# Sheet1.net
KiCad netlist of a schematic drawn in Altium Designer
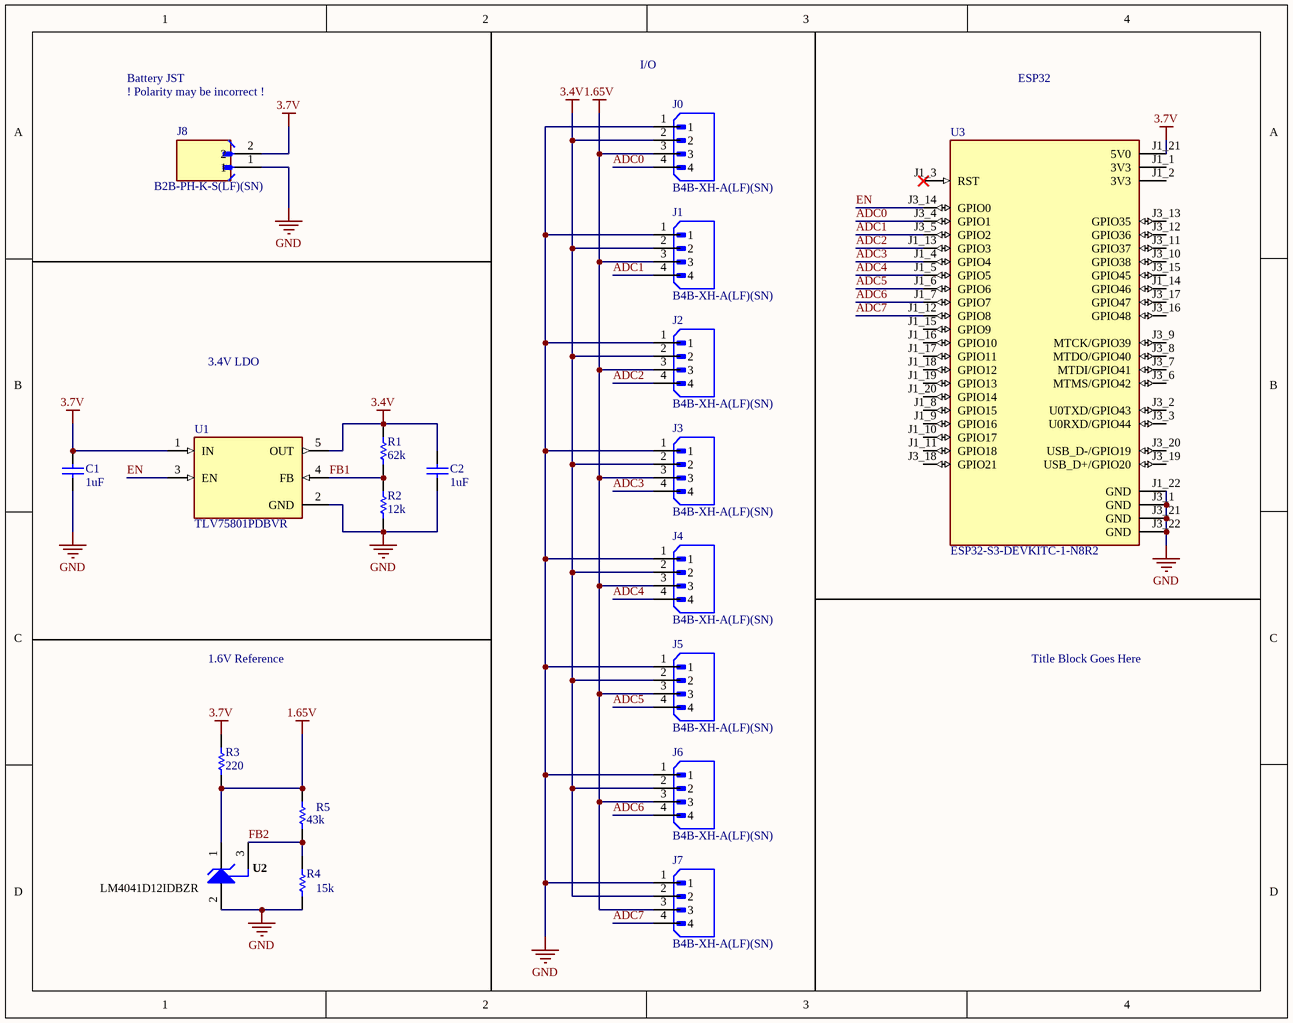
[diagram p0: Sheet1.SchDoc]

(export (version "E")
  (design (tool "Eeschema 10.0.6"))
  (components
    (comp (ref "C1")
      (value "1uF")
      (footprint "CAPC3216X110X50LL20T25")
      (description "Chip Capacitor, 1 uF, +/- 10%, 50 V, -55 to 125 degC, 1206 (3216 Metric), RoHS, Tape and Reel")
      (fields (field (name "MANUFACTURER") "Kemet") (field (name "TOLERANCE") "10%"))
      (libsource (lib "Altium Content Vault") (part "CAP-NP-2"))
    )
    (comp (ref "C2")
      (value "1uF")
      (footprint "CAPC3216X110X50LL20T25")
      (description "Chip Capacitor, 1 uF, +/- 10%, 50 V, -55 to 125 degC, 1206 (3216 Metric), RoHS, Tape and Reel")
      (fields (field (name "MANUFACTURER") "Kemet") (field (name "TOLERANCE") "10%"))
      (libsource (lib "Altium Content Vault") (part "CAP-NP-2"))
    )
    (comp (ref "J0")
      (value "B4B-XH-A(LF)(SN)")
      (footprint "JST_B4B-XH-A(LF)(SN)")
      (description "Connector Header Through Hole 4 position 0.098 (2.50mm)")
      (fields (field (name "MF") "JST Sales"))
      (libsource (lib "B4B-XH-A_LF__SN_") (part "B4B-XH-A(LF)(SN)"))
    )
    (comp (ref "J1")
      (value "B4B-XH-A(LF)(SN)")
      (footprint "JST_B4B-XH-A(LF)(SN)")
      (description "Connector Header Through Hole 4 position 0.098 (2.50mm)")
      (fields (field (name "MF") "JST Sales"))
      (libsource (lib "B4B-XH-A_LF__SN_") (part "B4B-XH-A(LF)(SN)"))
    )
    (comp (ref "J2")
      (value "B4B-XH-A(LF)(SN)")
      (footprint "JST_B4B-XH-A(LF)(SN)")
      (description "Connector Header Through Hole 4 position 0.098 (2.50mm)")
      (fields (field (name "MF") "JST Sales"))
      (libsource (lib "B4B-XH-A_LF__SN_") (part "B4B-XH-A(LF)(SN)"))
    )
    (comp (ref "J3")
      (value "B4B-XH-A(LF)(SN)")
      (footprint "JST_B4B-XH-A(LF)(SN)")
      (description "Connector Header Through Hole 4 position 0.098 (2.50mm)")
      (fields (field (name "MF") "JST Sales"))
      (libsource (lib "B4B-XH-A_LF__SN_") (part "B4B-XH-A(LF)(SN)"))
    )
    (comp (ref "J4")
      (value "B4B-XH-A(LF)(SN)")
      (footprint "JST_B4B-XH-A(LF)(SN)")
      (description "Connector Header Through Hole 4 position 0.098 (2.50mm)")
      (fields (field (name "MF") "JST Sales"))
      (libsource (lib "B4B-XH-A_LF__SN_") (part "B4B-XH-A(LF)(SN)"))
    )
    (comp (ref "J5")
      (value "B4B-XH-A(LF)(SN)")
      (footprint "JST_B4B-XH-A(LF)(SN)")
      (description "Connector Header Through Hole 4 position 0.098 (2.50mm)")
      (fields (field (name "MF") "JST Sales"))
      (libsource (lib "B4B-XH-A_LF__SN_") (part "B4B-XH-A(LF)(SN)"))
    )
    (comp (ref "J6")
      (value "B4B-XH-A(LF)(SN)")
      (footprint "JST_B4B-XH-A(LF)(SN)")
      (description "Connector Header Through Hole 4 position 0.098 (2.50mm)")
      (fields (field (name "MF") "JST Sales"))
      (libsource (lib "B4B-XH-A_LF__SN_") (part "B4B-XH-A(LF)(SN)"))
    )
    (comp (ref "J7")
      (value "B4B-XH-A(LF)(SN)")
      (footprint "JST_B4B-XH-A(LF)(SN)")
      (description "Connector Header Through Hole 4 position 0.098 (2.50mm)")
      (fields (field (name "MF") "JST Sales"))
      (libsource (lib "B4B-XH-A_LF__SN_") (part "B4B-XH-A(LF)(SN)"))
    )
    (comp (ref "J8")
      (value "B2B-PH-K-S(LF)(SN)")
      (footprint "JST_B2B-PH-K-S(LF)(SN)")
      (description "Connector Header Through Hole 2 position 0.079 (2.00mm)")
      (fields (field (name "MF") "JST") (field (name "MP") "B2B-PH-K-S (LF)(SN)"))
      (libsource (lib "B2B-PH-K-S_LF__SN_") (part "B2B-PH-K-S(LF)(SN)"))
    )
    (comp (ref "R1")
      (value "62k")
      (footprint "RESC3216X70X50LL20T25")
      (fields (field (name "PART NUMBER") "ERA8AEB623V") (field (name "MANUFACTURER") "Panasonic"))
      (libsource (lib "Altium Content Vault") (part "RES"))
    )
    (comp (ref "R2")
      (value "12k")
      (footprint "RESC3216X70X50NL20T25")
      (fields (field (name "PART NUMBER") "ERA8AEB123V") (field (name "MANUFACTURER") "Panasonic"))
      (libsource (lib "Altium Content Vault") (part "RES"))
    )
    (comp (ref "R3")
      (value "220")
      (footprint "RESC3216X60X45ML10T20")
      (fields (field (name "MANUFACTURER") "Vishay Dale") (field (name "PART NUMBER") "CRCW1206220RFKEA"))
      (libsource (lib "Altium Content Vault") (part "RES"))
    )
    (comp (ref "R4")
      (value "15k")
      (footprint "RESC3216X60X45LL10T20")
      (fields (field (name "PART NUMBER") "CRCW120615K0FKEA") (field (name "MANUFACTURER") "Vishay Dale"))
      (libsource (lib "Altium Content Vault") (part "RES"))
    )
    (comp (ref "R5")
      (value "43k")
      (footprint "RESC1206(3216)_N")
      (description "43K 0.25W 5% 1206 (3216 Metric)  SMD")
      (fields (field (name "TOLERANCE") "5 %") (field (name "POWER") "0.25 W"))
      (libsource (lib "Altium Content Vault") (part "RES"))
    )
    (comp (ref "U1")
      (value "TLV75801PDBVR")
      (footprint "SOT95P280X145-5N")
      (description "500-mA, low-IQ, high-accuracy, adjustable ultra-low-dropout voltage regulator with enable")
      (fields (field (name "MF") "Texas Instruments"))
      (libsource (lib "TLV75801PDBVR") (part "TLV75801PDBVR"))
    )
    (comp (ref "U2")
      (value "LM4041D12IDBZR")
      (footprint "DBZ0003A_L")
      (fields (field (name "MANUFACTURER") "Texas Instruments"))
      (libsource (lib "Altium Content Vault") (part "TI-LM4041D12DBZ3"))
    )
    (comp (ref "U3")
      (value "ESP32-S3-DEVKITC-1-N8R2")
      (footprint "XCVR_ESP32-S3-DEVKITC-1-N8R2")
      (fields (field (name "MF") "Espressif Systems"))
      (libsource (lib "ESP32-S3-DEVKITC-1-N8R2") (part "ESP32-S3-DEVKITC-1-N8R2"))
    )
  )
  (nets
    (net (code "1") (name "/ADC0") (class "Default")
      (node (ref "J0") (pin "4") (pinfunction "4_4") (pintype "passive"))
      (node (ref "U3") (pin "J3_4") (pinfunction "GPIO1_J3_4") (pintype "bidirectional"))
    )
    (net (code "2") (name "/ADC1") (class "Default")
      (node (ref "J1") (pin "4") (pinfunction "4_4") (pintype "passive"))
      (node (ref "U3") (pin "J3_5") (pinfunction "GPIO2_J3_5") (pintype "bidirectional"))
    )
    (net (code "3") (name "/ADC2") (class "Default")
      (node (ref "J2") (pin "4") (pinfunction "4_4") (pintype "passive"))
      (node (ref "U3") (pin "J1_13") (pinfunction "GPIO3_J1_13") (pintype "bidirectional"))
    )
    (net (code "4") (name "/ADC3") (class "Default")
      (node (ref "J3") (pin "4") (pinfunction "4_4") (pintype "passive"))
      (node (ref "U3") (pin "J1_4") (pinfunction "GPIO4_J1_4") (pintype "bidirectional"))
    )
    (net (code "5") (name "/ADC4") (class "Default")
      (node (ref "J4") (pin "4") (pinfunction "4_4") (pintype "passive"))
      (node (ref "U3") (pin "J1_5") (pinfunction "GPIO5_J1_5") (pintype "bidirectional"))
    )
    (net (code "6") (name "/ADC5") (class "Default")
      (node (ref "J5") (pin "4") (pinfunction "4_4") (pintype "passive"))
      (node (ref "U3") (pin "J1_6") (pinfunction "GPIO6_J1_6") (pintype "bidirectional"))
    )
    (net (code "7") (name "/ADC6") (class "Default")
      (node (ref "J6") (pin "4") (pinfunction "4_4") (pintype "passive"))
      (node (ref "U3") (pin "J1_7") (pinfunction "GPIO7_J1_7") (pintype "bidirectional"))
    )
    (net (code "8") (name "/ADC7") (class "Default")
      (node (ref "J7") (pin "4") (pinfunction "4_4") (pintype "passive"))
      (node (ref "U3") (pin "J1_12") (pinfunction "GPIO8_J1_12") (pintype "bidirectional"))
    )
    (net (code "9") (name "/EN") (class "Default")
      (node (ref "U1") (pin "3") (pinfunction "EN_3") (pintype "input"))
      (node (ref "U3") (pin "J3_14") (pinfunction "GPIO0_J3_14") (pintype "bidirectional"))
    )
    (net (code "10") (name "/FB1") (class "Default")
      (node (ref "R1") (pin "1") (pinfunction "1_1") (pintype "passive"))
      (node (ref "R2") (pin "2") (pinfunction "2_2") (pintype "passive"))
      (node (ref "U1") (pin "4") (pinfunction "FB_4") (pintype "input"))
    )
    (net (code "11") (name "/FB2") (class "Default")
      (node (ref "R4") (pin "2") (pinfunction "2_2") (pintype "passive"))
      (node (ref "R5") (pin "1") (pinfunction "1_1") (pintype "passive"))
      (node (ref "U2") (pin "3") (pinfunction "NC_3") (pintype "passive"))
    )
    (net (code "12") (name "1.65V") (class "Default")
      (node (ref "J0") (pin "3") (pinfunction "3_3") (pintype "passive"))
      (node (ref "J1") (pin "3") (pinfunction "3_3") (pintype "passive"))
      (node (ref "J2") (pin "3") (pinfunction "3_3") (pintype "passive"))
      (node (ref "J3") (pin "3") (pinfunction "3_3") (pintype "passive"))
      (node (ref "J4") (pin "3") (pinfunction "3_3") (pintype "passive"))
      (node (ref "J5") (pin "3") (pinfunction "3_3") (pintype "passive"))
      (node (ref "J6") (pin "3") (pinfunction "3_3") (pintype "passive"))
      (node (ref "J7") (pin "3") (pinfunction "3_3") (pintype "passive"))
      (node (ref "R3") (pin "2") (pinfunction "2_2") (pintype "passive"))
      (node (ref "R5") (pin "2") (pinfunction "2_2") (pintype "passive"))
      (node (ref "U2") (pin "1") (pinfunction "CATHODE_1") (pintype "passive"))
    )
    (net (code "13") (name "3.4V") (class "Default")
      (node (ref "C2") (pin "1") (pinfunction "1_1") (pintype "passive"))
      (node (ref "J0") (pin "2") (pinfunction "2_2") (pintype "passive"))
      (node (ref "J1") (pin "2") (pinfunction "2_2") (pintype "passive"))
      (node (ref "J2") (pin "2") (pinfunction "2_2") (pintype "passive"))
      (node (ref "J3") (pin "2") (pinfunction "2_2") (pintype "passive"))
      (node (ref "J4") (pin "2") (pinfunction "2_2") (pintype "passive"))
      (node (ref "J5") (pin "2") (pinfunction "2_2") (pintype "passive"))
      (node (ref "J6") (pin "2") (pinfunction "2_2") (pintype "passive"))
      (node (ref "J7") (pin "2") (pinfunction "2_2") (pintype "passive"))
      (node (ref "R1") (pin "2") (pinfunction "2_2") (pintype "passive"))
      (node (ref "U1") (pin "5") (pinfunction "OUT_5") (pintype "output"))
    )
    (net (code "14") (name "3.7V") (class "Default")
      (node (ref "C1") (pin "2") (pinfunction "2_2") (pintype "passive"))
      (node (ref "J8") (pin "2") (pinfunction "2_2") (pintype "passive"))
      (node (ref "R3") (pin "1") (pinfunction "1_1") (pintype "passive"))
      (node (ref "U1") (pin "1") (pinfunction "IN_1") (pintype "input"))
      (node (ref "U3") (pin "J1_21") (pinfunction "5V0_J1_21") (pintype "power_in"))
    )
    (net (code "15") (name "GND") (class "Default")
      (node (ref "C1") (pin "1") (pinfunction "1_1") (pintype "passive"))
      (node (ref "C2") (pin "2") (pinfunction "2_2") (pintype "passive"))
      (node (ref "J0") (pin "1") (pinfunction "1_1") (pintype "passive"))
      (node (ref "J1") (pin "1") (pinfunction "1_1") (pintype "passive"))
      (node (ref "J2") (pin "1") (pinfunction "1_1") (pintype "passive"))
      (node (ref "J3") (pin "1") (pinfunction "1_1") (pintype "passive"))
      (node (ref "J4") (pin "1") (pinfunction "1_1") (pintype "passive"))
      (node (ref "J5") (pin "1") (pinfunction "1_1") (pintype "passive"))
      (node (ref "J6") (pin "1") (pinfunction "1_1") (pintype "passive"))
      (node (ref "J7") (pin "1") (pinfunction "1_1") (pintype "passive"))
      (node (ref "J8") (pin "1") (pinfunction "1_1") (pintype "passive"))
      (node (ref "R2") (pin "1") (pinfunction "1_1") (pintype "passive"))
      (node (ref "R4") (pin "1") (pinfunction "1_1") (pintype "passive"))
      (node (ref "U1") (pin "2") (pinfunction "GND_2") (pintype "power_in"))
      (node (ref "U2") (pin "2") (pinfunction "ANODE_2") (pintype "passive"))
      (node (ref "U3") (pin "J1_22") (pinfunction "GND_J1_22") (pintype "power_in"))
      (node (ref "U3") (pin "J3_1") (pinfunction "GND_J3_1") (pintype "power_in"))
      (node (ref "U3") (pin "J3_21") (pinfunction "GND_J3_21") (pintype "power_in"))
      (node (ref "U3") (pin "J3_22") (pinfunction "GND_J3_22") (pintype "power_in"))
    )
    (net (code "16") (name "unconnected-(U3-3V3-PadJ1_1)") (class "Default")
      (node (ref "U3") (pin "J1_1") (pinfunction "3V3_J1_1") (pintype "power_in"))
    )
    (net (code "17") (name "unconnected-(U3-3V3-PadJ1_2)") (class "Default")
      (node (ref "U3") (pin "J1_2") (pinfunction "3V3_J1_2") (pintype "power_in"))
    )
    (net (code "18") (name "unconnected-(U3-GPIO9-PadJ1_15)") (class "Default")
      (node (ref "U3") (pin "J1_15") (pinfunction "GPIO9_J1_15") (pintype "bidirectional"))
    )
    (net (code "19") (name "unconnected-(U3-GPIO10-PadJ1_16)") (class "Default")
      (node (ref "U3") (pin "J1_16") (pinfunction "GPIO10_J1_16") (pintype "bidirectional"))
    )
    (net (code "20") (name "unconnected-(U3-GPIO11-PadJ1_17)") (class "Default")
      (node (ref "U3") (pin "J1_17") (pinfunction "GPIO11_J1_17") (pintype "bidirectional"))
    )
    (net (code "21") (name "unconnected-(U3-GPIO12-PadJ1_18)") (class "Default")
      (node (ref "U3") (pin "J1_18") (pinfunction "GPIO12_J1_18") (pintype "bidirectional"))
    )
    (net (code "22") (name "unconnected-(U3-GPIO13-PadJ1_19)") (class "Default")
      (node (ref "U3") (pin "J1_19") (pinfunction "GPIO13_J1_19") (pintype "bidirectional"))
    )
    (net (code "23") (name "unconnected-(U3-GPIO14-PadJ1_20)") (class "Default")
      (node (ref "U3") (pin "J1_20") (pinfunction "GPIO14_J1_20") (pintype "bidirectional"))
    )
    (net (code "24") (name "unconnected-(U3-GPIO15-PadJ1_8)") (class "Default")
      (node (ref "U3") (pin "J1_8") (pinfunction "GPIO15_J1_8") (pintype "bidirectional"))
    )
    (net (code "25") (name "unconnected-(U3-GPIO16-PadJ1_9)") (class "Default")
      (node (ref "U3") (pin "J1_9") (pinfunction "GPIO16_J1_9") (pintype "bidirectional"))
    )
    (net (code "26") (name "unconnected-(U3-GPIO17-PadJ1_10)") (class "Default")
      (node (ref "U3") (pin "J1_10") (pinfunction "GPIO17_J1_10") (pintype "bidirectional"))
    )
    (net (code "27") (name "unconnected-(U3-GPIO18-PadJ1_11)") (class "Default")
      (node (ref "U3") (pin "J1_11") (pinfunction "GPIO18_J1_11") (pintype "bidirectional"))
    )
    (net (code "28") (name "unconnected-(U3-GPIO21-PadJ3_18)") (class "Default")
      (node (ref "U3") (pin "J3_18") (pinfunction "GPIO21_J3_18") (pintype "bidirectional"))
    )
    (net (code "29") (name "unconnected-(U3-GPIO35-PadJ3_13)") (class "Default")
      (node (ref "U3") (pin "J3_13") (pinfunction "GPIO35_J3_13") (pintype "bidirectional"))
    )
    (net (code "30") (name "unconnected-(U3-GPIO36-PadJ3_12)") (class "Default")
      (node (ref "U3") (pin "J3_12") (pinfunction "GPIO36_J3_12") (pintype "bidirectional"))
    )
    (net (code "31") (name "unconnected-(U3-GPIO37-PadJ3_11)") (class "Default")
      (node (ref "U3") (pin "J3_11") (pinfunction "GPIO37_J3_11") (pintype "bidirectional"))
    )
    (net (code "32") (name "unconnected-(U3-GPIO38-PadJ3_10)") (class "Default")
      (node (ref "U3") (pin "J3_10") (pinfunction "GPIO38_J3_10") (pintype "bidirectional"))
    )
    (net (code "33") (name "unconnected-(U3-GPIO45-PadJ3_15)") (class "Default")
      (node (ref "U3") (pin "J3_15") (pinfunction "GPIO45_J3_15") (pintype "bidirectional"))
    )
    (net (code "34") (name "unconnected-(U3-GPIO46-PadJ1_14)") (class "Default")
      (node (ref "U3") (pin "J1_14") (pinfunction "GPIO46_J1_14") (pintype "bidirectional"))
    )
    (net (code "35") (name "unconnected-(U3-GPIO47-PadJ3_17)") (class "Default")
      (node (ref "U3") (pin "J3_17") (pinfunction "GPIO47_J3_17") (pintype "bidirectional"))
    )
    (net (code "36") (name "unconnected-(U3-GPIO48-PadJ3_16)") (class "Default")
      (node (ref "U3") (pin "J3_16") (pinfunction "GPIO48_J3_16") (pintype "bidirectional"))
    )
    (net (code "37") (name "unconnected-(U3-MTCK{slash}GPIO39-PadJ3_9)") (class "Default")
      (node (ref "U3") (pin "J3_9") (pinfunction "MTCK/GPIO39_J3_9") (pintype "bidirectional"))
    )
    (net (code "38") (name "unconnected-(U3-MTDI{slash}GPIO41-PadJ3_7)") (class "Default")
      (node (ref "U3") (pin "J3_7") (pinfunction "MTDI/GPIO41_J3_7") (pintype "bidirectional"))
    )
    (net (code "39") (name "unconnected-(U3-MTDO{slash}GPIO40-PadJ3_8)") (class "Default")
      (node (ref "U3") (pin "J3_8") (pinfunction "MTDO/GPIO40_J3_8") (pintype "bidirectional"))
    )
    (net (code "40") (name "unconnected-(U3-MTMS{slash}GPIO42-PadJ3_6)") (class "Default")
      (node (ref "U3") (pin "J3_6") (pinfunction "MTMS/GPIO42_J3_6") (pintype "bidirectional"))
    )
    (net (code "41") (name "unconnected-(U3-RST-PadJ1_3)") (class "Default")
      (node (ref "U3") (pin "J1_3") (pinfunction "RST_J1_3") (pintype "input+no_connect"))
    )
    (net (code "42") (name "unconnected-(U3-U0RXD{slash}GPIO44-PadJ3_3)") (class "Default")
      (node (ref "U3") (pin "J3_3") (pinfunction "U0RXD/GPIO44_J3_3") (pintype "bidirectional"))
    )
    (net (code "43") (name "unconnected-(U3-U0TXD{slash}GPIO43-PadJ3_2)") (class "Default")
      (node (ref "U3") (pin "J3_2") (pinfunction "U0TXD/GPIO43_J3_2") (pintype "bidirectional"))
    )
    (net (code "44") (name "unconnected-(U3-USB_D+{slash}GPIO20-PadJ3_19)") (class "Default")
      (node (ref "U3") (pin "J3_19") (pinfunction "USB_D+/GPIO20_J3_19") (pintype "bidirectional"))
    )
    (net (code "45") (name "unconnected-(U3-USB_D-{slash}GPIO19-PadJ3_20)") (class "Default")
      (node (ref "U3") (pin "J3_20") (pinfunction "USB_D-/GPIO19_J3_20") (pintype "bidirectional"))
    )
  )
)
